# Scott.net
KiCad netlist of a schematic drawn in EAGLE
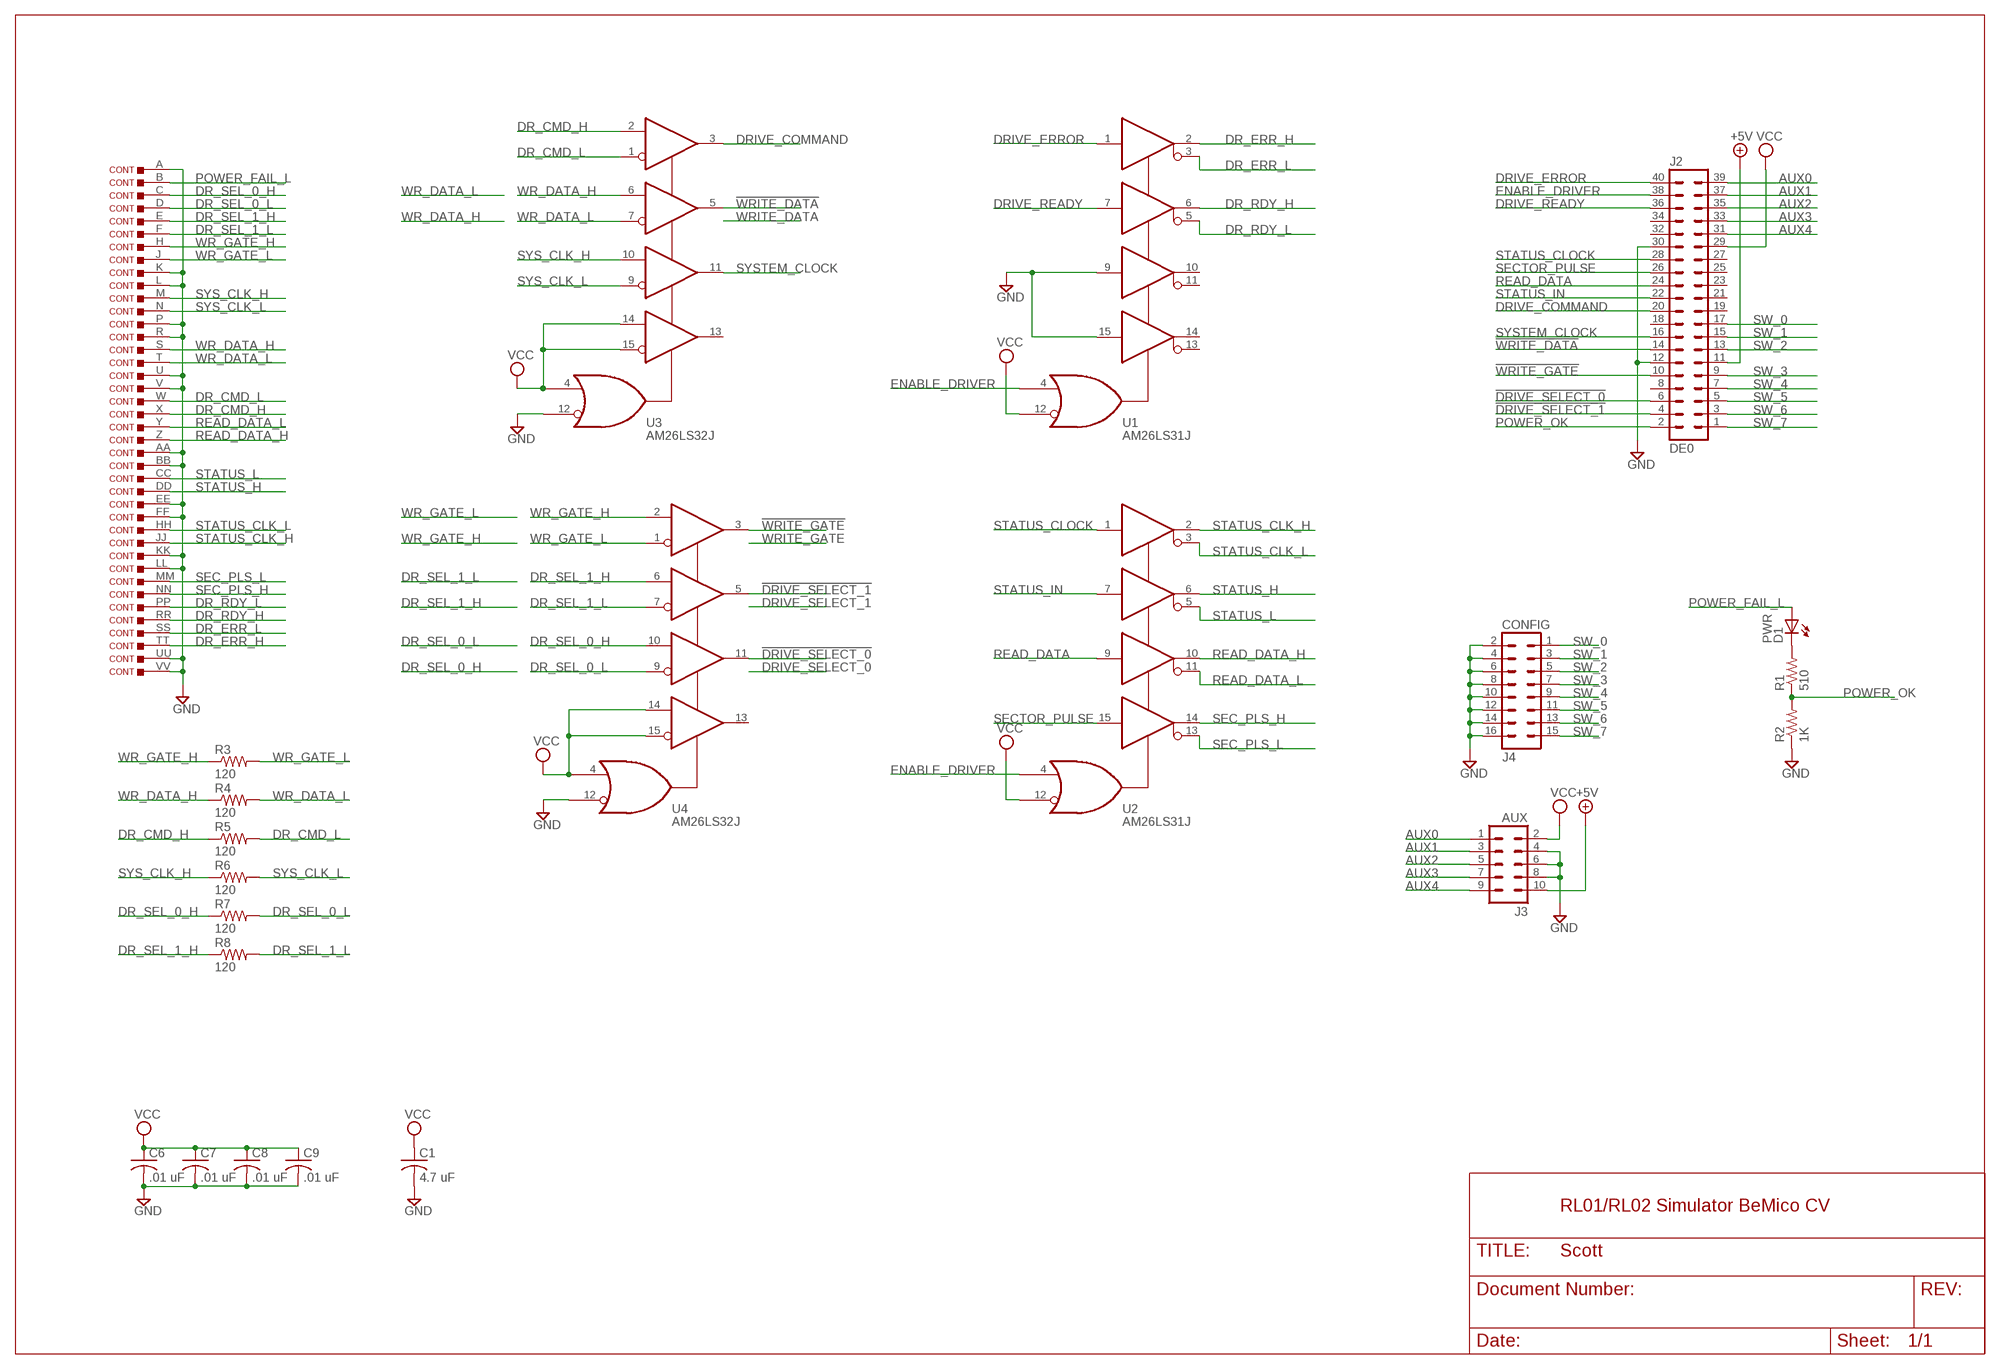
[diagram p0: schematic, sheet 1]

(export (version "E")
  (design (tool "Eeschema 10.0.6"))
  (components
    (comp (ref "C1")
      (value "4.7 uF")
      (footprint "eagle-import:C1210K")
      (libsource (lib "eagle-import") (part "C-USC1210K"))
    )
    (comp (ref "C6")
      (value ".01 uF")
      (footprint "eagle-import:C0805")
      (libsource (lib "eagle-import") (part "C-USC0805"))
    )
    (comp (ref "C7")
      (value ".01 uF")
      (footprint "eagle-import:C0805")
      (libsource (lib "eagle-import") (part "C-USC0805"))
    )
    (comp (ref "C8")
      (value ".01 uF")
      (footprint "eagle-import:C0805")
      (libsource (lib "eagle-import") (part "C-USC0805"))
    )
    (comp (ref "C9")
      (value ".01 uF")
      (footprint "eagle-import:C0805")
      (libsource (lib "eagle-import") (part "C-USC0805"))
    )
    (comp (ref "CONT")
      (value "DEC40PINSV")
      (footprint "eagle-import:DEC40PINV")
      (libsource (lib "eagle-import") (part "DEC40PINSV"))
    )
    (comp (ref "D1")
      (value "PWR")
      (footprint "eagle-import:SML0805")
      (libsource (lib "eagle-import") (part "LEDSML0805"))
    )
    (comp (ref "J2")
      (value "DE0")
      (footprint "eagle-import:MA20-2")
      (libsource (lib "eagle-import") (part "MA20-2"))
    )
    (comp (ref "J3")
      (value "AUX")
      (footprint "eagle-import:MA05-2")
      (libsource (lib "eagle-import") (part "MA05-2"))
    )
    (comp (ref "J4")
      (value "CONFIG")
      (footprint "eagle-import:MA08-2")
      (libsource (lib "eagle-import") (part "MA08-2"))
    )
    (comp (ref "R1")
      (value "510")
      (footprint "eagle-import:M0805")
      (libsource (lib "eagle-import") (part "R-US_M0805"))
    )
    (comp (ref "R2")
      (value "1K")
      (footprint "eagle-import:M0805")
      (libsource (lib "eagle-import") (part "R-US_M0805"))
    )
    (comp (ref "R3")
      (value "120")
      (footprint "eagle-import:0204V")
      (libsource (lib "eagle-import") (part "R-US_0204/2V"))
    )
    (comp (ref "R4")
      (value "120")
      (footprint "eagle-import:0204V")
      (libsource (lib "eagle-import") (part "R-US_0204/2V"))
    )
    (comp (ref "R5")
      (value "120")
      (footprint "eagle-import:0204V")
      (libsource (lib "eagle-import") (part "R-US_0204/2V"))
    )
    (comp (ref "R6")
      (value "120")
      (footprint "eagle-import:0204V")
      (libsource (lib "eagle-import") (part "R-US_0204/2V"))
    )
    (comp (ref "R7")
      (value "120")
      (footprint "eagle-import:0204V")
      (libsource (lib "eagle-import") (part "R-US_0204/2V"))
    )
    (comp (ref "R8")
      (value "120")
      (footprint "eagle-import:0204V")
      (libsource (lib "eagle-import") (part "R-US_0204/2V"))
    )
    (comp (ref "U1")
      (value "AM26LS31J")
      (footprint "eagle-import:SO16")
      (libsource (lib "eagle-import") (part "AM26LS31J"))
    )
    (comp (ref "U2")
      (value "AM26LS31J")
      (footprint "eagle-import:SO16")
      (libsource (lib "eagle-import") (part "AM26LS31J"))
    )
    (comp (ref "U3")
      (value "AM26LS32J")
      (footprint "eagle-import:SO16")
      (libsource (lib "eagle-import") (part "AM26LS32J"))
    )
    (comp (ref "U4")
      (value "AM26LS32J")
      (footprint "eagle-import:SO16")
      (libsource (lib "eagle-import") (part "AM26LS32J"))
    )
  )
  (nets
    (net (code "1") (name "+5V") (class "Default")
      (node (ref "J2") (pin "11") (pinfunction "11_11") (pintype "passive"))
      (node (ref "J3") (pin "10") (pinfunction "10_10") (pintype "passive"))
    )
    (net (code "2") (name "/AUX0") (class "Default")
      (node (ref "J2") (pin "39") (pinfunction "39_39") (pintype "passive"))
      (node (ref "J3") (pin "1") (pinfunction "1_1") (pintype "passive"))
    )
    (net (code "3") (name "/AUX1") (class "Default")
      (node (ref "J2") (pin "37") (pinfunction "37_37") (pintype "passive"))
      (node (ref "J3") (pin "3") (pinfunction "3_3") (pintype "passive"))
    )
    (net (code "4") (name "/AUX2") (class "Default")
      (node (ref "J2") (pin "35") (pinfunction "35_35") (pintype "passive"))
      (node (ref "J3") (pin "5") (pinfunction "5_5") (pintype "passive"))
    )
    (net (code "5") (name "/AUX3") (class "Default")
      (node (ref "J2") (pin "33") (pinfunction "33_33") (pintype "passive"))
      (node (ref "J3") (pin "7") (pinfunction "7_7") (pintype "passive"))
    )
    (net (code "6") (name "/AUX4") (class "Default")
      (node (ref "J2") (pin "31") (pinfunction "31_31") (pintype "passive"))
      (node (ref "J3") (pin "9") (pinfunction "9_9") (pintype "passive"))
    )
    (net (code "7") (name "/DRIVE_COMMAND") (class "Default")
      (node (ref "J2") (pin "20") (pinfunction "20_20") (pintype "passive"))
      (node (ref "U3") (pin "3") (pinfunction "Y1_3") (pintype "output"))
    )
    (net (code "8") (name "/DRIVE_ERROR") (class "Default")
      (node (ref "J2") (pin "40") (pinfunction "40_40") (pintype "passive"))
      (node (ref "U1") (pin "1") (pinfunction "A1_1") (pintype "input"))
    )
    (net (code "9") (name "/DRIVE_READY") (class "Default")
      (node (ref "J2") (pin "36") (pinfunction "36_36") (pintype "passive"))
      (node (ref "U1") (pin "7") (pinfunction "A2_7") (pintype "input"))
    )
    (net (code "12") (name "/DR_CMD_H") (class "Default")
      (node (ref "CONT") (pin "X") (pinfunction "P$2_X") (pintype "passive"))
      (node (ref "R5") (pin "1") (pinfunction "1_1") (pintype "passive"))
      (node (ref "U3") (pin "2") (pinfunction "P1_2") (pintype "input"))
    )
    (net (code "13") (name "/DR_CMD_L") (class "Default")
      (node (ref "CONT") (pin "W") (pinfunction "P$2_W") (pintype "passive"))
      (node (ref "R5") (pin "2") (pinfunction "2_2") (pintype "passive"))
      (node (ref "U3") (pin "1") (pinfunction "N1_1") (pintype "input"))
    )
    (net (code "14") (name "/DR_ERR_H") (class "Default")
      (node (ref "CONT") (pin "TT") (pinfunction "P$2_TT") (pintype "passive"))
      (node (ref "U1") (pin "2") (pinfunction "Y1_2") (pintype "output"))
    )
    (net (code "15") (name "/DR_ERR_L") (class "Default")
      (node (ref "CONT") (pin "SS") (pinfunction "P$2_SS") (pintype "passive"))
      (node (ref "U1") (pin "3") (pinfunction "Z1_3") (pintype "output"))
    )
    (net (code "16") (name "/DR_RDY_H") (class "Default")
      (node (ref "CONT") (pin "RR") (pinfunction "P$2_RR") (pintype "passive"))
      (node (ref "U1") (pin "6") (pinfunction "Y2_6") (pintype "output"))
    )
    (net (code "17") (name "/DR_RDY_L") (class "Default")
      (node (ref "CONT") (pin "PP") (pinfunction "P$2_PP") (pintype "passive"))
      (node (ref "U1") (pin "5") (pinfunction "Z2_5") (pintype "output"))
    )
    (net (code "18") (name "/DR_SEL_0_H") (class "Default")
      (node (ref "CONT") (pin "C") (pinfunction "P$2_C") (pintype "passive"))
      (node (ref "R7") (pin "1") (pinfunction "1_1") (pintype "passive"))
      (node (ref "U4") (pin "10") (pinfunction "P3_10") (pintype "input"))
    )
    (net (code "19") (name "/DR_SEL_0_L") (class "Default")
      (node (ref "CONT") (pin "D") (pinfunction "P$2_D") (pintype "passive"))
      (node (ref "R7") (pin "2") (pinfunction "2_2") (pintype "passive"))
      (node (ref "U4") (pin "9") (pinfunction "N3_9") (pintype "input"))
    )
    (net (code "20") (name "/DR_SEL_1_H") (class "Default")
      (node (ref "CONT") (pin "E") (pinfunction "P$2_E") (pintype "passive"))
      (node (ref "R8") (pin "1") (pinfunction "1_1") (pintype "passive"))
      (node (ref "U4") (pin "6") (pinfunction "P2_6") (pintype "input"))
    )
    (net (code "21") (name "/DR_SEL_1_L") (class "Default")
      (node (ref "CONT") (pin "F") (pinfunction "P$2_F") (pintype "passive"))
      (node (ref "R8") (pin "2") (pinfunction "2_2") (pintype "passive"))
      (node (ref "U4") (pin "7") (pinfunction "N2_7") (pintype "input"))
    )
    (net (code "22") (name "/ENABLE_DRIVER") (class "Default")
      (node (ref "J2") (pin "38") (pinfunction "38_38") (pintype "passive"))
      (node (ref "U1") (pin "4") (pinfunction "G_4") (pintype "input"))
      (node (ref "U2") (pin "4") (pinfunction "G_4") (pintype "input"))
    )
    (net (code "23") (name "/POWER_FAIL_L") (class "Default")
      (node (ref "CONT") (pin "B") (pinfunction "P$2_B") (pintype "passive"))
      (node (ref "D1") (pin "A") (pinfunction "A_A") (pintype "passive"))
    )
    (net (code "24") (name "/POWER_OK") (class "Default")
      (node (ref "J2") (pin "2") (pinfunction "2_2") (pintype "passive"))
      (node (ref "R1") (pin "1") (pinfunction "1_1") (pintype "passive"))
      (node (ref "R2") (pin "2") (pinfunction "2_2") (pintype "passive"))
    )
    (net (code "25") (name "/READ_DATA") (class "Default")
      (node (ref "J2") (pin "24") (pinfunction "24_24") (pintype "passive"))
      (node (ref "U2") (pin "9") (pinfunction "A3_9") (pintype "input"))
    )
    (net (code "26") (name "/READ_DATA_H") (class "Default")
      (node (ref "CONT") (pin "Z") (pinfunction "P$2_Z") (pintype "passive"))
      (node (ref "U2") (pin "10") (pinfunction "Y3_10") (pintype "output"))
    )
    (net (code "27") (name "/READ_DATA_L") (class "Default")
      (node (ref "CONT") (pin "Y") (pinfunction "P$2_Y") (pintype "passive"))
      (node (ref "U2") (pin "11") (pinfunction "Z3_11") (pintype "output"))
    )
    (net (code "28") (name "/SECTOR_PULSE") (class "Default")
      (node (ref "J2") (pin "26") (pinfunction "26_26") (pintype "passive"))
      (node (ref "U2") (pin "15") (pinfunction "A4_15") (pintype "input"))
    )
    (net (code "29") (name "/SEC_PLS_H") (class "Default")
      (node (ref "CONT") (pin "NN") (pinfunction "P$2_NN") (pintype "passive"))
      (node (ref "U2") (pin "14") (pinfunction "Y4_14") (pintype "output"))
    )
    (net (code "30") (name "/SEC_PLS_L") (class "Default")
      (node (ref "CONT") (pin "MM") (pinfunction "P$2_MM") (pintype "passive"))
      (node (ref "U2") (pin "13") (pinfunction "Z4_13") (pintype "output"))
    )
    (net (code "31") (name "/STATUS_CLK_H") (class "Default")
      (node (ref "CONT") (pin "JJ") (pinfunction "P$2_JJ") (pintype "passive"))
      (node (ref "U2") (pin "2") (pinfunction "Y1_2") (pintype "output"))
    )
    (net (code "32") (name "/STATUS_CLK_L") (class "Default")
      (node (ref "CONT") (pin "HH") (pinfunction "P$2_HH") (pintype "passive"))
      (node (ref "U2") (pin "3") (pinfunction "Z1_3") (pintype "output"))
    )
    (net (code "33") (name "/STATUS_CLOCK") (class "Default")
      (node (ref "J2") (pin "28") (pinfunction "28_28") (pintype "passive"))
      (node (ref "U2") (pin "1") (pinfunction "A1_1") (pintype "input"))
    )
    (net (code "34") (name "/STATUS_H") (class "Default")
      (node (ref "CONT") (pin "DD") (pinfunction "P$2_DD") (pintype "passive"))
      (node (ref "U2") (pin "6") (pinfunction "Y2_6") (pintype "output"))
    )
    (net (code "35") (name "/STATUS_IN") (class "Default")
      (node (ref "J2") (pin "22") (pinfunction "22_22") (pintype "passive"))
      (node (ref "U2") (pin "7") (pinfunction "A2_7") (pintype "input"))
    )
    (net (code "36") (name "/STATUS_L") (class "Default")
      (node (ref "CONT") (pin "CC") (pinfunction "P$2_CC") (pintype "passive"))
      (node (ref "U2") (pin "5") (pinfunction "Z2_5") (pintype "output"))
    )
    (net (code "37") (name "/SW_0") (class "Default")
      (node (ref "J2") (pin "17") (pinfunction "17_17") (pintype "passive"))
      (node (ref "J4") (pin "1") (pinfunction "1_1") (pintype "passive"))
    )
    (net (code "38") (name "/SW_1") (class "Default")
      (node (ref "J2") (pin "15") (pinfunction "15_15") (pintype "passive"))
      (node (ref "J4") (pin "3") (pinfunction "3_3") (pintype "passive"))
    )
    (net (code "39") (name "/SW_2") (class "Default")
      (node (ref "J2") (pin "13") (pinfunction "13_13") (pintype "passive"))
      (node (ref "J4") (pin "5") (pinfunction "5_5") (pintype "passive"))
    )
    (net (code "40") (name "/SW_3") (class "Default")
      (node (ref "J2") (pin "9") (pinfunction "9_9") (pintype "passive"))
      (node (ref "J4") (pin "7") (pinfunction "7_7") (pintype "passive"))
    )
    (net (code "41") (name "/SW_4") (class "Default")
      (node (ref "J2") (pin "7") (pinfunction "7_7") (pintype "passive"))
      (node (ref "J4") (pin "9") (pinfunction "9_9") (pintype "passive"))
    )
    (net (code "42") (name "/SW_5") (class "Default")
      (node (ref "J2") (pin "5") (pinfunction "5_5") (pintype "passive"))
      (node (ref "J4") (pin "11") (pinfunction "11_11") (pintype "passive"))
    )
    (net (code "43") (name "/SW_6") (class "Default")
      (node (ref "J2") (pin "3") (pinfunction "3_3") (pintype "passive"))
      (node (ref "J4") (pin "13") (pinfunction "13_13") (pintype "passive"))
    )
    (net (code "44") (name "/SW_7") (class "Default")
      (node (ref "J2") (pin "1") (pinfunction "1_1") (pintype "passive"))
      (node (ref "J4") (pin "15") (pinfunction "15_15") (pintype "passive"))
    )
    (net (code "45") (name "/SYSTEM_CLOCK") (class "Default")
      (node (ref "J2") (pin "16") (pinfunction "16_16") (pintype "passive"))
      (node (ref "U3") (pin "11") (pinfunction "Y3_11") (pintype "output"))
    )
    (net (code "46") (name "/SYS_CLK_H") (class "Default")
      (node (ref "CONT") (pin "M") (pinfunction "P$2_M") (pintype "passive"))
      (node (ref "R6") (pin "1") (pinfunction "1_1") (pintype "passive"))
      (node (ref "U3") (pin "10") (pinfunction "P3_10") (pintype "input"))
    )
    (net (code "47") (name "/SYS_CLK_L") (class "Default")
      (node (ref "CONT") (pin "N") (pinfunction "P$2_N") (pintype "passive"))
      (node (ref "R6") (pin "2") (pinfunction "2_2") (pintype "passive"))
      (node (ref "U3") (pin "9") (pinfunction "N3_9") (pintype "input"))
    )
    (net (code "50") (name "/WR_DATA_H") (class "Default")
      (node (ref "CONT") (pin "S") (pinfunction "P$2_S") (pintype "passive"))
      (node (ref "R4") (pin "1") (pinfunction "1_1") (pintype "passive"))
      (node (ref "U3") (pin "6") (pinfunction "P2_6") (pintype "input"))
    )
    (net (code "51") (name "/WR_DATA_L") (class "Default")
      (node (ref "CONT") (pin "T") (pinfunction "P$2_T") (pintype "passive"))
      (node (ref "R4") (pin "2") (pinfunction "2_2") (pintype "passive"))
      (node (ref "U3") (pin "7") (pinfunction "N2_7") (pintype "input"))
    )
    (net (code "52") (name "/WR_GATE_H") (class "Default")
      (node (ref "CONT") (pin "H") (pinfunction "P$2_H") (pintype "passive"))
      (node (ref "R3") (pin "1") (pinfunction "1_1") (pintype "passive"))
      (node (ref "U4") (pin "2") (pinfunction "P1_2") (pintype "input"))
    )
    (net (code "53") (name "/WR_GATE_L") (class "Default")
      (node (ref "CONT") (pin "J") (pinfunction "P$2_J") (pintype "passive"))
      (node (ref "R3") (pin "2") (pinfunction "2_2") (pintype "passive"))
      (node (ref "U4") (pin "1") (pinfunction "N1_1") (pintype "input"))
    )
    (net (code "54") (name "/~{DRIVE_SELECT_0}") (class "Default")
      (node (ref "J2") (pin "6") (pinfunction "6_6") (pintype "passive"))
      (node (ref "U4") (pin "11") (pinfunction "Y3_11") (pintype "output"))
    )
    (net (code "55") (name "/~{DRIVE_SELECT_1}") (class "Default")
      (node (ref "J2") (pin "4") (pinfunction "4_4") (pintype "passive"))
      (node (ref "U4") (pin "5") (pinfunction "Y2_5") (pintype "output"))
    )
    (net (code "56") (name "/~{WRITE_DATA}") (class "Default")
      (node (ref "J2") (pin "14") (pinfunction "14_14") (pintype "passive"))
      (node (ref "U3") (pin "5") (pinfunction "Y2_5") (pintype "output"))
    )
    (net (code "57") (name "/~{WRITE_GATE}") (class "Default")
      (node (ref "J2") (pin "10") (pinfunction "10_10") (pintype "passive"))
      (node (ref "U4") (pin "3") (pinfunction "Y1_3") (pintype "output"))
    )
    (net (code "58") (name "GND") (class "Default")
      (node (ref "C1") (pin "2") (pinfunction "2_2") (pintype "passive"))
      (node (ref "C6") (pin "2") (pinfunction "2_2") (pintype "passive"))
      (node (ref "C7") (pin "2") (pinfunction "2_2") (pintype "passive"))
      (node (ref "C8") (pin "2") (pinfunction "2_2") (pintype "passive"))
      (node (ref "C9") (pin "2") (pinfunction "2_2") (pintype "passive"))
      (node (ref "CONT") (pin "A") (pinfunction "P$2_A") (pintype "passive"))
      (node (ref "CONT") (pin "AA") (pinfunction "P$2_AA") (pintype "passive"))
      (node (ref "CONT") (pin "BB") (pinfunction "P$2_BB") (pintype "passive"))
      (node (ref "CONT") (pin "EE") (pinfunction "P$2_EE") (pintype "passive"))
      (node (ref "CONT") (pin "FF") (pinfunction "P$2_FF") (pintype "passive"))
      (node (ref "CONT") (pin "K") (pinfunction "P$2_K") (pintype "passive"))
      (node (ref "CONT") (pin "KK") (pinfunction "P$2_KK") (pintype "passive"))
      (node (ref "CONT") (pin "L") (pinfunction "P$2_L") (pintype "passive"))
      (node (ref "CONT") (pin "LL") (pinfunction "P$2_LL") (pintype "passive"))
      (node (ref "CONT") (pin "P") (pinfunction "P$2_P") (pintype "passive"))
      (node (ref "CONT") (pin "R") (pinfunction "P$2_R") (pintype "passive"))
      (node (ref "CONT") (pin "U") (pinfunction "P$2_U") (pintype "passive"))
      (node (ref "CONT") (pin "UU") (pinfunction "P$2_UU") (pintype "passive"))
      (node (ref "CONT") (pin "V") (pinfunction "P$2_V") (pintype "passive"))
      (node (ref "CONT") (pin "VV") (pinfunction "P$2_VV") (pintype "passive"))
      (node (ref "J2") (pin "12") (pinfunction "12_12") (pintype "passive"))
      (node (ref "J2") (pin "30") (pinfunction "30_30") (pintype "passive"))
      (node (ref "J3") (pin "4") (pinfunction "4_4") (pintype "passive"))
      (node (ref "J3") (pin "6") (pinfunction "6_6") (pintype "passive"))
      (node (ref "J3") (pin "8") (pinfunction "8_8") (pintype "passive"))
      (node (ref "J4") (pin "10") (pinfunction "10_10") (pintype "passive"))
      (node (ref "J4") (pin "12") (pinfunction "12_12") (pintype "passive"))
      (node (ref "J4") (pin "14") (pinfunction "14_14") (pintype "passive"))
      (node (ref "J4") (pin "16") (pinfunction "16_16") (pintype "passive"))
      (node (ref "J4") (pin "2") (pinfunction "2_2") (pintype "passive"))
      (node (ref "J4") (pin "4") (pinfunction "4_4") (pintype "passive"))
      (node (ref "J4") (pin "6") (pinfunction "6_6") (pintype "passive"))
      (node (ref "J4") (pin "8") (pinfunction "8_8") (pintype "passive"))
      (node (ref "R2") (pin "1") (pinfunction "1_1") (pintype "passive"))
      (node (ref "U1") (pin "15") (pinfunction "A4_15") (pintype "input"))
      (node (ref "U1") (pin "9") (pinfunction "A3_9") (pintype "input"))
      (node (ref "U3") (pin "12") (pinfunction "~{G}_12") (pintype "input"))
      (node (ref "U4") (pin "12") (pinfunction "~{G}_12") (pintype "input"))
    )
    (net (code "59") (name "Net-(D1-PadC)") (class "Default")
      (node (ref "D1") (pin "C") (pinfunction "C_C") (pintype "passive"))
      (node (ref "R1") (pin "2") (pinfunction "2_2") (pintype "passive"))
    )
    (net (code "60") (name "VCC") (class "Default")
      (node (ref "C1") (pin "1") (pinfunction "1_1") (pintype "passive"))
      (node (ref "C6") (pin "1") (pinfunction "1_1") (pintype "passive"))
      (node (ref "C7") (pin "1") (pinfunction "1_1") (pintype "passive"))
      (node (ref "C8") (pin "1") (pinfunction "1_1") (pintype "passive"))
      (node (ref "C9") (pin "1") (pinfunction "1_1") (pintype "passive"))
      (node (ref "J2") (pin "29") (pinfunction "29_29") (pintype "passive"))
      (node (ref "J3") (pin "2") (pinfunction "2_2") (pintype "passive"))
      (node (ref "U1") (pin "12") (pinfunction "~{G}_12") (pintype "input"))
      (node (ref "U2") (pin "12") (pinfunction "~{G}_12") (pintype "input"))
      (node (ref "U3") (pin "14") (pinfunction "P4_14") (pintype "input"))
      (node (ref "U3") (pin "15") (pinfunction "N4_15") (pintype "input"))
      (node (ref "U3") (pin "4") (pinfunction "G_4") (pintype "input"))
      (node (ref "U4") (pin "14") (pinfunction "P4_14") (pintype "input"))
      (node (ref "U4") (pin "15") (pinfunction "N4_15") (pintype "input"))
      (node (ref "U4") (pin "4") (pinfunction "G_4") (pintype "input"))
    )
    (net (code "61") (name "unconnected-(J2-Pad8)") (class "Default")
      (node (ref "J2") (pin "8") (pinfunction "8_8") (pintype "passive"))
    )
    (net (code "62") (name "unconnected-(J2-Pad18)") (class "Default")
      (node (ref "J2") (pin "18") (pinfunction "18_18") (pintype "passive"))
    )
    (net (code "63") (name "unconnected-(J2-Pad19)") (class "Default")
      (node (ref "J2") (pin "19") (pinfunction "19_19") (pintype "passive"))
    )
    (net (code "64") (name "unconnected-(J2-Pad21)") (class "Default")
      (node (ref "J2") (pin "21") (pinfunction "21_21") (pintype "passive"))
    )
    (net (code "65") (name "unconnected-(J2-Pad23)") (class "Default")
      (node (ref "J2") (pin "23") (pinfunction "23_23") (pintype "passive"))
    )
    (net (code "66") (name "unconnected-(J2-Pad25)") (class "Default")
      (node (ref "J2") (pin "25") (pinfunction "25_25") (pintype "passive"))
    )
    (net (code "67") (name "unconnected-(J2-Pad27)") (class "Default")
      (node (ref "J2") (pin "27") (pinfunction "27_27") (pintype "passive"))
    )
    (net (code "68") (name "unconnected-(J2-Pad32)") (class "Default")
      (node (ref "J2") (pin "32") (pinfunction "32_32") (pintype "passive"))
    )
    (net (code "69") (name "unconnected-(J2-Pad34)") (class "Default")
      (node (ref "J2") (pin "34") (pinfunction "34_34") (pintype "passive"))
    )
    (net (code "70") (name "unconnected-(U1A-Y3-Pad10)") (class "Default")
      (node (ref "U1") (pin "10") (pinfunction "Y3_10") (pintype "output"))
    )
    (net (code "71") (name "unconnected-(U1A-Y4-Pad14)") (class "Default")
      (node (ref "U1") (pin "14") (pinfunction "Y4_14") (pintype "output"))
    )
    (net (code "72") (name "unconnected-(U1A-Z3-Pad11)") (class "Default")
      (node (ref "U1") (pin "11") (pinfunction "Z3_11") (pintype "output"))
    )
    (net (code "73") (name "unconnected-(U1A-Z4-Pad13)") (class "Default")
      (node (ref "U1") (pin "13") (pinfunction "Z4_13") (pintype "output"))
    )
    (net (code "74") (name "unconnected-(U3A-Y4-Pad13)") (class "Default")
      (node (ref "U3") (pin "13") (pinfunction "Y4_13") (pintype "output"))
    )
    (net (code "75") (name "unconnected-(U4A-Y4-Pad13)") (class "Default")
      (node (ref "U4") (pin "13") (pinfunction "Y4_13") (pintype "output"))
    )
  )
)
